# pb_debug.net
KiCad netlist of a schematic drawn in EAGLE
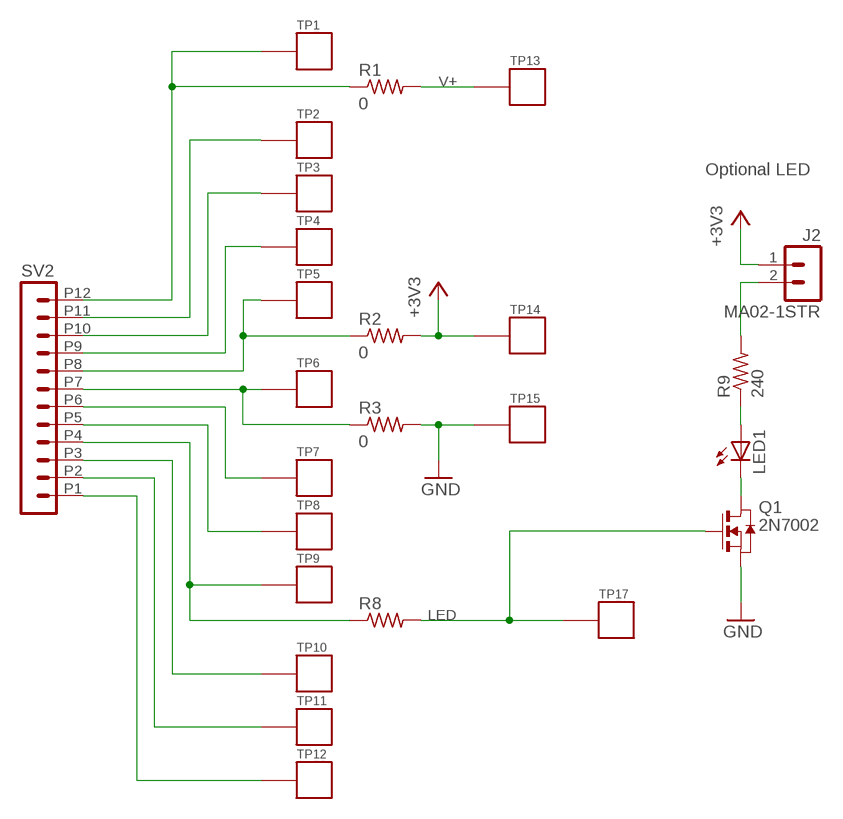
[diagram p0: schematic, sheet 1]
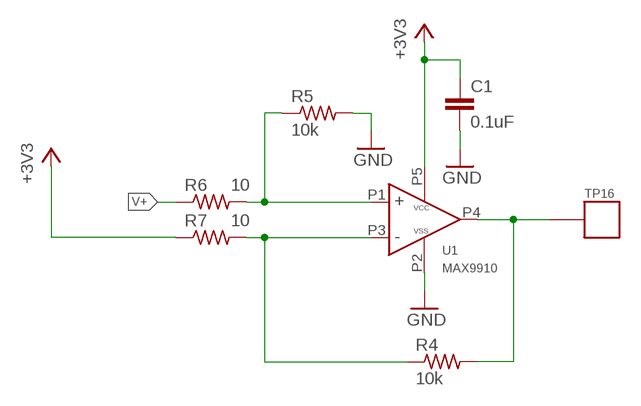
[diagram p1: schematic, sheet 2]
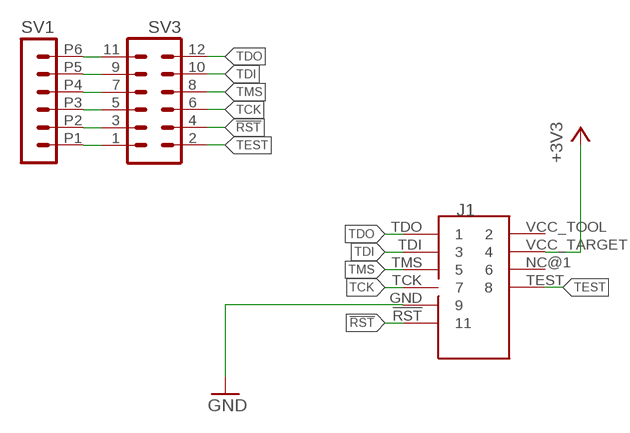
[diagram p2: schematic, sheet 3]

(export (version "E")
  (design (tool "Eeschema 10.0.6"))
  (components
    (comp (ref "J2")
      (value "MA02-1STR")
      (footprint "eagle-import:MA02-1")
      (libsource (lib "eagle-import") (part "MA02-1STR"))
    )
    (comp (ref "LED1")
      (value "LED0603")
      (footprint "eagle-import:LED-0603")
      (libsource (lib "eagle-import") (part "LED0603"))
    )
    (comp (ref "Q1")
      (value "2N7002")
      (footprint "eagle-import:SC-70-3")
      (libsource (lib "eagle-import") (part "2N7002"))
    )
    (comp (ref "R1")
      (value "0")
      (footprint "eagle-import:R0603")
      (libsource (lib "eagle-import") (part "R-US_R0603"))
    )
    (comp (ref "R2")
      (value "0")
      (footprint "eagle-import:R0603")
      (libsource (lib "eagle-import") (part "R-US_R0603"))
    )
    (comp (ref "R3")
      (value "0")
      (footprint "eagle-import:R0603")
      (libsource (lib "eagle-import") (part "R-US_R0603"))
    )
    (comp (ref "R8")
      (value "R-US_R0603")
      (footprint "eagle-import:R0603")
      (libsource (lib "eagle-import") (part "R-US_R0603"))
    )
    (comp (ref "R9")
      (value "240")
      (footprint "eagle-import:R0603")
      (libsource (lib "eagle-import") (part "R-US_R0603"))
    )
    (comp (ref "SV2")
      (value "MA12-11MM27_LONG")
      (footprint "eagle-import:MA12-1_1MM27_LONG")
      (libsource (lib "eagle-import") (part "MA12-11MM27_LONG"))
    )
    (comp (ref "TP1")
      (value "TP_MULT")
      (footprint "eagle-import:TP_MULT")
      (libsource (lib "eagle-import") (part "TP_MULT"))
    )
    (comp (ref "TP2")
      (value "TP_MULT")
      (footprint "eagle-import:TP_MULT")
      (libsource (lib "eagle-import") (part "TP_MULT"))
    )
    (comp (ref "TP3")
      (value "TP_MULT")
      (footprint "eagle-import:TP_MULT")
      (libsource (lib "eagle-import") (part "TP_MULT"))
    )
    (comp (ref "TP4")
      (value "TP_MULT")
      (footprint "eagle-import:TP_MULT")
      (libsource (lib "eagle-import") (part "TP_MULT"))
    )
    (comp (ref "TP5")
      (value "TP_MULT")
      (footprint "eagle-import:TP_MULT")
      (libsource (lib "eagle-import") (part "TP_MULT"))
    )
    (comp (ref "TP6")
      (value "TP_MULT")
      (footprint "eagle-import:TP_MULT")
      (libsource (lib "eagle-import") (part "TP_MULT"))
    )
    (comp (ref "TP7")
      (value "TP_MULT")
      (footprint "eagle-import:TP_MULT")
      (libsource (lib "eagle-import") (part "TP_MULT"))
    )
    (comp (ref "TP8")
      (value "TP_MULT")
      (footprint "eagle-import:TP_MULT")
      (libsource (lib "eagle-import") (part "TP_MULT"))
    )
    (comp (ref "TP9")
      (value "TP_MULT")
      (footprint "eagle-import:TP_MULT")
      (libsource (lib "eagle-import") (part "TP_MULT"))
    )
    (comp (ref "TP10")
      (value "TP_MULT")
      (footprint "eagle-import:TP_MULT")
      (libsource (lib "eagle-import") (part "TP_MULT"))
    )
    (comp (ref "TP11")
      (value "TP_MULT")
      (footprint "eagle-import:TP_MULT")
      (libsource (lib "eagle-import") (part "TP_MULT"))
    )
    (comp (ref "TP12")
      (value "TP_MULT")
      (footprint "eagle-import:TP_MULT")
      (libsource (lib "eagle-import") (part "TP_MULT"))
    )
    (comp (ref "TP13")
      (value "TP_STD")
      (footprint "eagle-import:TP")
      (libsource (lib "eagle-import") (part "TP_STD"))
    )
    (comp (ref "TP14")
      (value "TP_STD")
      (footprint "eagle-import:TP")
      (libsource (lib "eagle-import") (part "TP_STD"))
    )
    (comp (ref "TP15")
      (value "TP_STD")
      (footprint "eagle-import:TP")
      (libsource (lib "eagle-import") (part "TP_STD"))
    )
    (comp (ref "TP17")
      (value "TP_STD")
      (footprint "eagle-import:TP")
      (libsource (lib "eagle-import") (part "TP_STD"))
    )
    (comp (ref "C1")
      (value "0.1uF")
      (footprint "eagle-import:C0603")
      (libsource (lib "eagle-import") (part "C-EUC0603"))
    )
    (comp (ref "R4")
      (value "10k")
      (footprint "eagle-import:R0603")
      (libsource (lib "eagle-import") (part "R-US_R0603"))
    )
    (comp (ref "R5")
      (value "10k")
      (footprint "eagle-import:R0603")
      (libsource (lib "eagle-import") (part "R-US_R0603"))
    )
    (comp (ref "R6")
      (value "10")
      (footprint "eagle-import:R0603")
      (libsource (lib "eagle-import") (part "R-US_R0603"))
    )
    (comp (ref "R7")
      (value "10")
      (footprint "eagle-import:R0603")
      (libsource (lib "eagle-import") (part "R-US_R0603"))
    )
    (comp (ref "TP16")
      (value "TP_MULT")
      (footprint "eagle-import:TP_MULT")
      (libsource (lib "eagle-import") (part "TP_MULT"))
    )
    (comp (ref "U1")
      (value "MAX9910")
      (footprint "eagle-import:SC70-5")
      (libsource (lib "eagle-import") (part "MAX9910"))
    )
    (comp (ref "J1")
      (value "JTAG_14PIN_FULL")
      (footprint "eagle-import:MA14-JTAG")
      (libsource (lib "eagle-import") (part "JTAG_14PIN_FULL"))
    )
    (comp (ref "SV1")
      (value "MA06-11MM27_LONG")
      (footprint "eagle-import:MA06-1_1MM27_LONG")
      (libsource (lib "eagle-import") (part "MA06-11MM27_LONG"))
    )
    (comp (ref "SV3")
      (value "MA06-2")
      (footprint "eagle-import:MA06-2")
      (libsource (lib "eagle-import") (part "MA06-2"))
    )
  )
  (nets
    (net (code "1") (name "+3V3") (class "Default")
      (node (ref "C1") (pin "1") (pinfunction "1_1") (pintype "passive"))
      (node (ref "J1") (pin "VCC_TARGET") (pinfunction "4_VCC_TARGET") (pintype "bidirectional"))
      (node (ref "J2") (pin "1") (pinfunction "1_1") (pintype "passive"))
      (node (ref "R2") (pin "2") (pinfunction "2_2") (pintype "passive"))
      (node (ref "R7") (pin "1") (pinfunction "1_1") (pintype "passive"))
      (node (ref "TP14") (pin "P$1") (pinfunction "P$1_P$1") (pintype "bidirectional"))
      (node (ref "U1") (pin "P5") (pinfunction "VCC_P5") (pintype "bidirectional"))
    )
    (net (code "2") (name "GND") (class "Default")
      (node (ref "C1") (pin "2") (pinfunction "2_2") (pintype "passive"))
      (node (ref "J1") (pin "GND") (pinfunction "9_GND") (pintype "bidirectional"))
      (node (ref "Q1") (pin "P2") (pinfunction "S_P2") (pintype "passive"))
      (node (ref "R3") (pin "2") (pinfunction "2_2") (pintype "passive"))
      (node (ref "R5") (pin "2") (pinfunction "2_2") (pintype "passive"))
      (node (ref "TP15") (pin "P$1") (pinfunction "P$1_P$1") (pintype "bidirectional"))
      (node (ref "U1") (pin "P2") (pinfunction "VSS_P2") (pintype "bidirectional"))
    )
    (net (code "3") (name "LED") (class "Default")
      (node (ref "Q1") (pin "P1") (pinfunction "G_P1") (pintype "passive"))
      (node (ref "R8") (pin "2") (pinfunction "2_2") (pintype "passive"))
      (node (ref "TP17") (pin "P$1") (pinfunction "P$1_P$1") (pintype "bidirectional"))
    )
    (net (code "4") (name "Net-(J2-Pad2)") (class "Default")
      (node (ref "J2") (pin "2") (pinfunction "2_2") (pintype "passive"))
      (node (ref "R9") (pin "2") (pinfunction "2_2") (pintype "passive"))
    )
    (net (code "5") (name "Net-(LED1-PadA)") (class "Default")
      (node (ref "LED1") (pin "A") (pinfunction "A_A") (pintype "passive"))
      (node (ref "R9") (pin "1") (pinfunction "1_1") (pintype "passive"))
    )
    (net (code "6") (name "Net-(Q1-D)") (class "Default")
      (node (ref "LED1") (pin "C") (pinfunction "C_C") (pintype "passive"))
      (node (ref "Q1") (pin "P3") (pinfunction "D_P3") (pintype "passive"))
    )
    (net (code "7") (name "Net-(SV1-1)") (class "Default")
      (node (ref "SV1") (pin "P1") (pinfunction "1_P1") (pintype "passive"))
      (node (ref "SV3") (pin "1") (pinfunction "1_1") (pintype "passive"))
    )
    (net (code "8") (name "Net-(SV1-2)") (class "Default")
      (node (ref "SV1") (pin "P2") (pinfunction "2_P2") (pintype "passive"))
      (node (ref "SV3") (pin "3") (pinfunction "3_3") (pintype "passive"))
    )
    (net (code "9") (name "Net-(SV1-3)") (class "Default")
      (node (ref "SV1") (pin "P3") (pinfunction "3_P3") (pintype "passive"))
      (node (ref "SV3") (pin "5") (pinfunction "5_5") (pintype "passive"))
    )
    (net (code "10") (name "Net-(SV1-4)") (class "Default")
      (node (ref "SV1") (pin "P4") (pinfunction "4_P4") (pintype "passive"))
      (node (ref "SV3") (pin "7") (pinfunction "7_7") (pintype "passive"))
    )
    (net (code "11") (name "Net-(SV1-5)") (class "Default")
      (node (ref "SV1") (pin "P5") (pinfunction "5_P5") (pintype "passive"))
      (node (ref "SV3") (pin "9") (pinfunction "9_9") (pintype "passive"))
    )
    (net (code "12") (name "Net-(SV1-6)") (class "Default")
      (node (ref "SV1") (pin "P6") (pinfunction "6_P6") (pintype "passive"))
      (node (ref "SV3") (pin "11") (pinfunction "11_11") (pintype "passive"))
    )
    (net (code "13") (name "Net-(SV2-1)") (class "Default")
      (node (ref "SV2") (pin "P1") (pinfunction "1_P1") (pintype "passive"))
      (node (ref "TP12") (pin "P$1") (pinfunction "P$1_P$1") (pintype "bidirectional"))
    )
    (net (code "14") (name "Net-(SV2-2)") (class "Default")
      (node (ref "SV2") (pin "P2") (pinfunction "2_P2") (pintype "passive"))
      (node (ref "TP11") (pin "P$1") (pinfunction "P$1_P$1") (pintype "bidirectional"))
    )
    (net (code "15") (name "Net-(SV2-3)") (class "Default")
      (node (ref "SV2") (pin "P3") (pinfunction "3_P3") (pintype "passive"))
      (node (ref "TP10") (pin "P$1") (pinfunction "P$1_P$1") (pintype "bidirectional"))
    )
    (net (code "16") (name "Net-(SV2-4)") (class "Default")
      (node (ref "R8") (pin "1") (pinfunction "1_1") (pintype "passive"))
      (node (ref "SV2") (pin "P4") (pinfunction "4_P4") (pintype "passive"))
      (node (ref "TP9") (pin "P$1") (pinfunction "P$1_P$1") (pintype "bidirectional"))
    )
    (net (code "17") (name "Net-(SV2-5)") (class "Default")
      (node (ref "SV2") (pin "P5") (pinfunction "5_P5") (pintype "passive"))
      (node (ref "TP8") (pin "P$1") (pinfunction "P$1_P$1") (pintype "bidirectional"))
    )
    (net (code "18") (name "Net-(SV2-6)") (class "Default")
      (node (ref "SV2") (pin "P6") (pinfunction "6_P6") (pintype "passive"))
      (node (ref "TP7") (pin "P$1") (pinfunction "P$1_P$1") (pintype "bidirectional"))
    )
    (net (code "19") (name "Net-(SV2-7)") (class "Default")
      (node (ref "R3") (pin "1") (pinfunction "1_1") (pintype "passive"))
      (node (ref "SV2") (pin "P7") (pinfunction "7_P7") (pintype "passive"))
      (node (ref "TP6") (pin "P$1") (pinfunction "P$1_P$1") (pintype "bidirectional"))
    )
    (net (code "20") (name "Net-(SV2-8)") (class "Default")
      (node (ref "R2") (pin "1") (pinfunction "1_1") (pintype "passive"))
      (node (ref "SV2") (pin "P8") (pinfunction "8_P8") (pintype "passive"))
      (node (ref "TP5") (pin "P$1") (pinfunction "P$1_P$1") (pintype "bidirectional"))
    )
    (net (code "21") (name "Net-(SV2-9)") (class "Default")
      (node (ref "SV2") (pin "P9") (pinfunction "9_P9") (pintype "passive"))
      (node (ref "TP4") (pin "P$1") (pinfunction "P$1_P$1") (pintype "bidirectional"))
    )
    (net (code "22") (name "Net-(SV2-10)") (class "Default")
      (node (ref "SV2") (pin "P10") (pinfunction "10_P10") (pintype "passive"))
      (node (ref "TP3") (pin "P$1") (pinfunction "P$1_P$1") (pintype "bidirectional"))
    )
    (net (code "23") (name "Net-(SV2-11)") (class "Default")
      (node (ref "SV2") (pin "P11") (pinfunction "11_P11") (pintype "passive"))
      (node (ref "TP2") (pin "P$1") (pinfunction "P$1_P$1") (pintype "bidirectional"))
    )
    (net (code "24") (name "Net-(SV2-12)") (class "Default")
      (node (ref "R1") (pin "1") (pinfunction "1_1") (pintype "passive"))
      (node (ref "SV2") (pin "P12") (pinfunction "12_P12") (pintype "passive"))
      (node (ref "TP1") (pin "P$1") (pinfunction "P$1_P$1") (pintype "bidirectional"))
    )
    (net (code "25") (name "Net-(U1-IN+)") (class "Default")
      (node (ref "R5") (pin "1") (pinfunction "1_1") (pintype "passive"))
      (node (ref "R6") (pin "2") (pinfunction "2_2") (pintype "passive"))
      (node (ref "U1") (pin "P1") (pinfunction "IN+_P1") (pintype "bidirectional"))
    )
    (net (code "26") (name "Net-(U1-IN-)") (class "Default")
      (node (ref "R4") (pin "1") (pinfunction "1_1") (pintype "passive"))
      (node (ref "R7") (pin "2") (pinfunction "2_2") (pintype "passive"))
      (node (ref "U1") (pin "P3") (pinfunction "IN-_P3") (pintype "bidirectional"))
    )
    (net (code "27") (name "Net-(U1-OUT)") (class "Default")
      (node (ref "R4") (pin "2") (pinfunction "2_2") (pintype "passive"))
      (node (ref "TP16") (pin "P$1") (pinfunction "P$1_P$1") (pintype "bidirectional"))
      (node (ref "U1") (pin "P4") (pinfunction "OUT_P4") (pintype "bidirectional"))
    )
    (net (code "28") (name "TCK") (class "Default")
      (node (ref "J1") (pin "TCK") (pinfunction "7_TCK") (pintype "bidirectional"))
      (node (ref "SV3") (pin "6") (pinfunction "6_6") (pintype "passive"))
    )
    (net (code "29") (name "TDI") (class "Default")
      (node (ref "J1") (pin "TDI") (pinfunction "3_TDI") (pintype "bidirectional"))
      (node (ref "SV3") (pin "10") (pinfunction "10_10") (pintype "passive"))
    )
    (net (code "30") (name "TDO") (class "Default")
      (node (ref "J1") (pin "TDO") (pinfunction "1_TDO") (pintype "bidirectional"))
      (node (ref "SV3") (pin "12") (pinfunction "12_12") (pintype "passive"))
    )
    (net (code "31") (name "TEST") (class "Default")
      (node (ref "J1") (pin "TEST") (pinfunction "8_TEST") (pintype "bidirectional"))
      (node (ref "SV3") (pin "2") (pinfunction "2_2") (pintype "passive"))
    )
    (net (code "32") (name "TMS") (class "Default")
      (node (ref "J1") (pin "TMS") (pinfunction "5_TMS") (pintype "bidirectional"))
      (node (ref "SV3") (pin "8") (pinfunction "8_8") (pintype "passive"))
    )
    (net (code "33") (name "V+") (class "Default")
      (node (ref "R1") (pin "2") (pinfunction "2_2") (pintype "passive"))
      (node (ref "R6") (pin "1") (pinfunction "1_1") (pintype "passive"))
      (node (ref "TP13") (pin "P$1") (pinfunction "P$1_P$1") (pintype "bidirectional"))
    )
    (net (code "34") (name "unconnected-(J1-2-PadVCC_TOOL)") (class "Default")
      (node (ref "J1") (pin "VCC_TOOL") (pinfunction "2_VCC_TOOL") (pintype "bidirectional"))
    )
    (net (code "35") (name "unconnected-(J1-6-PadNC@1)") (class "Default")
      (node (ref "J1") (pin "NC@1") (pinfunction "6_NC@1") (pintype "bidirectional"))
    )
    (net (code "36") (name "~{RST}") (class "Default")
      (node (ref "J1") (pin "!RST!") (pinfunction "11_!RST!") (pintype "bidirectional"))
      (node (ref "SV3") (pin "4") (pinfunction "4_4") (pintype "passive"))
    )
  )
)
